# MainBoard_PWR.net
KiCad netlist of a schematic drawn in Altium Designer
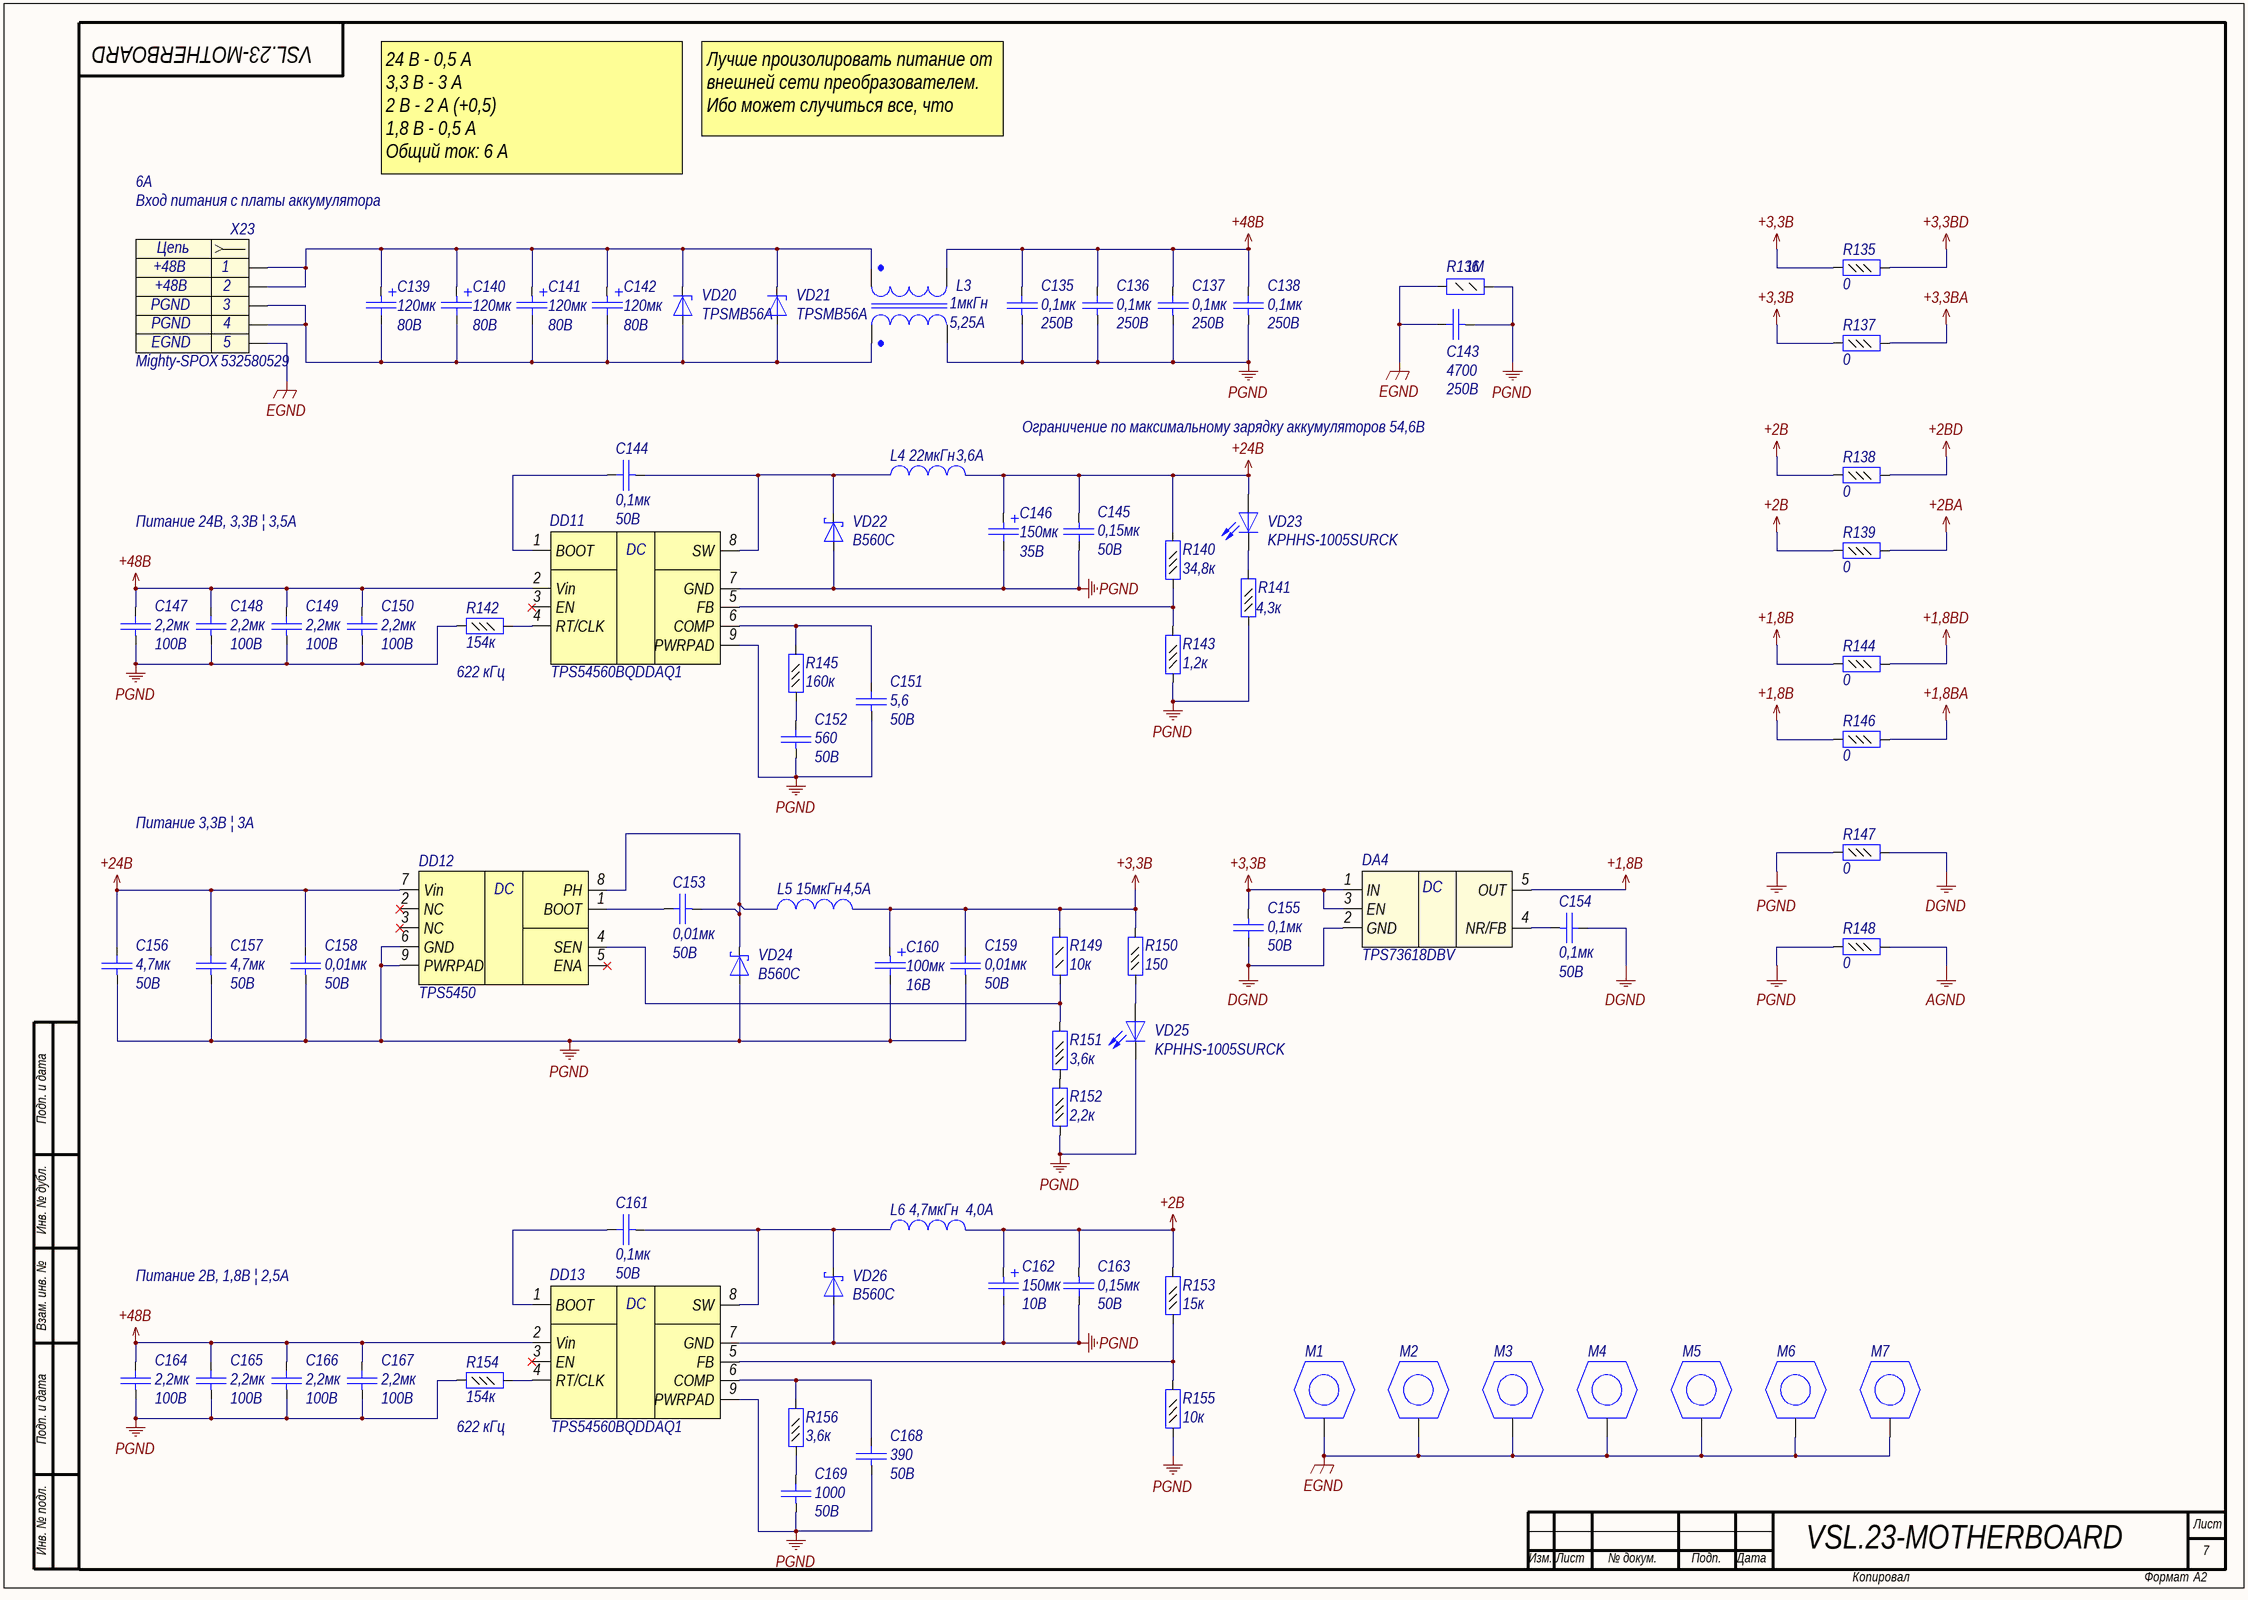
[diagram p0: MainBoard_PWR.SchDoc]

(export (version "E")
  (design (tool "Eeschema 10.0.6"))
  (components
    (comp (ref "C135")
      (value "0,1мк")
      (footprint "C1206")
      (description "Конденсатор")
      (fields
        (field (name "VOLTAGE") "250В")
        (field (name "PART NUMBER") "GRM31CR72E104K")
        (field (name "Comment") "Capacitor")
      )
      (libsource (lib "MOP44") (part "Capacitor"))
    )
    (comp (ref "C136")
      (value "0,1мк")
      (footprint "C1206")
      (description "Конденсатор")
      (fields
        (field (name "VOLTAGE") "250В")
        (field (name "PART NUMBER") "GRM31CR72E104K")
        (field (name "Comment") "Capacitor")
      )
      (libsource (lib "MOP44") (part "Capacitor"))
    )
    (comp (ref "C137")
      (value "0,1мк")
      (footprint "C1206")
      (description "Конденсатор")
      (fields
        (field (name "VOLTAGE") "250В")
        (field (name "PART NUMBER") "GRM31CR72E104K")
        (field (name "Comment") "Capacitor")
      )
      (libsource (lib "MOP44") (part "Capacitor"))
    )
    (comp (ref "C138")
      (value "0,1мк")
      (footprint "C1206")
      (description "Конденсатор")
      (fields
        (field (name "VOLTAGE") "250В")
        (field (name "PART NUMBER") "GRM31CR72E104K")
        (field (name "Comment") "Capacitor")
      )
      (libsource (lib "MOP44") (part "Capacitor"))
    )
    (comp (ref "C139")
      (value "120мк")
      (footprint "K50-35(8X20)_V")
      (description "Конденсатор полярный")
      (fields
        (field (name "VOLTAGE") "80В")
        (field (name "PART NUMBER") "EEU-FS1K121LB")
        (field (name "Comment") "Capacitor_pol")
      )
      (libsource (lib "MOP44") (part "Capacitor_pol"))
    )
    (comp (ref "C140")
      (value "120мк")
      (footprint "K50-35(8X20)_V")
      (description "Конденсатор полярный")
      (fields
        (field (name "VOLTAGE") "80В")
        (field (name "PART NUMBER") "EEU-FS1K121LB")
        (field (name "Comment") "Capacitor_pol")
      )
      (libsource (lib "MOP44") (part "Capacitor_pol"))
    )
    (comp (ref "C141")
      (value "120мк")
      (footprint "K50-35(8X20)_V")
      (description "Конденсатор полярный")
      (fields
        (field (name "VOLTAGE") "80В")
        (field (name "PART NUMBER") "EEU-FS1K121LB")
        (field (name "Comment") "Capacitor_pol")
      )
      (libsource (lib "MOP44") (part "Capacitor_pol"))
    )
    (comp (ref "C142")
      (value "120мк")
      (footprint "K50-35(8X20)_V")
      (description "Конденсатор полярный")
      (fields
        (field (name "VOLTAGE") "80В")
        (field (name "PART NUMBER") "EEU-FS1K121LB")
        (field (name "Comment") "Capacitor_pol")
      )
      (libsource (lib "MOP44") (part "Capacitor_pol"))
    )
    (comp (ref "C143")
      (value "4700")
      (footprint "C0805")
      (description "Конденсатор")
      (fields
        (field (name "VOLTAGE") "250В")
        (field (name "PART NUMBER") "GRM21AR72E472KW")
        (field (name "Comment") "Capacitor")
      )
      (libsource (lib "MOP44") (part "Capacitor"))
    )
    (comp (ref "C144")
      (value "0,1мк")
      (footprint "C0402")
      (description "Конденсатор")
      (fields (field (name "VOLTAGE") "50В") (field (name "PART NUMBER") "GRM155R71H104KE14D "))
      (libsource (lib "MOP44") (part "Capacitor"))
    )
    (comp (ref "C145")
      (value "0,15мк")
      (footprint "C1812")
      (description "Конденсатор")
      (fields (field (name "VOLTAGE") "50В") (field (name "PART NUMBER") "C4532C0G1H154J250KA "))
      (libsource (lib "MOP44") (part "Capacitor"))
    )
    (comp (ref "C146")
      (value "150мк")
      (footprint "Cap_SMD_radial_polar(8x10.2)")
      (description "Конденсатор полярный")
      (fields
        (field (name "VOLTAGE") "35В")
        (field (name "PART NUMBER") "EEH-ZE1V151V")
        (field (name "Comment") "Capacitor_pol")
      )
      (libsource (lib "MOP44") (part "Capacitor_pol"))
    )
    (comp (ref "C147")
      (value "2,2мк")
      (footprint "C1812")
      (description "Конденсатор")
      (fields (field (name "VOLTAGE") "100В") (field (name "PART NUMBER") "C4532X7R2A225M"))
      (libsource (lib "MOP44") (part "Capacitor"))
    )
    (comp (ref "C148")
      (value "2,2мк")
      (footprint "C1812")
      (description "Конденсатор")
      (fields (field (name "VOLTAGE") "100В") (field (name "PART NUMBER") "C4532X7R2A225M"))
      (libsource (lib "MOP44") (part "Capacitor"))
    )
    (comp (ref "C149")
      (value "2,2мк")
      (footprint "C1812")
      (description "Конденсатор")
      (fields (field (name "VOLTAGE") "100В") (field (name "PART NUMBER") "C4532X7R2A225M"))
      (libsource (lib "MOP44") (part "Capacitor"))
    )
    (comp (ref "C150")
      (value "2,2мк")
      (footprint "C1812")
      (description "Конденсатор")
      (fields (field (name "VOLTAGE") "100В") (field (name "PART NUMBER") "C4532X7R2A225M"))
      (libsource (lib "MOP44") (part "Capacitor"))
    )
    (comp (ref "C151")
      (value "5,6")
      (footprint "C0402")
      (description "Конденсатор")
      (fields (field (name "VOLTAGE") "50B") (field (name "PART NUMBER") "GRM1555C1H5R6C"))
      (libsource (lib "MOP44") (part "Capacitor"))
    )
    (comp (ref "C152")
      (value "560")
      (footprint "C0402")
      (description "Конденсатор")
      (fields (field (name "VOLTAGE") "50B") (field (name "PART NUMBER") "GRM1555C1H561J"))
      (libsource (lib "MOP44") (part "Capacitor"))
    )
    (comp (ref "C153")
      (value "0,01мк")
      (footprint "C0402")
      (description "Конденсатор")
      (fields (field (name "VOLTAGE") "50B") (field (name "PART NUMBER") "GRM155R71H103K"))
      (libsource (lib "MOP44") (part "Capacitor"))
    )
    (comp (ref "C154")
      (value "0,1мк")
      (footprint "C0402")
      (description "Конденсатор")
      (fields
        (field (name "VOLTAGE") "50В")
        (field (name "PART NUMBER") "GRM155R71H104KE14D ")
        (field (name "Comment") "Capacitor")
      )
      (libsource (lib "MOP44") (part "Capacitor"))
    )
    (comp (ref "C155")
      (value "0,1мк")
      (footprint "C0402")
      (description "Конденсатор")
      (fields
        (field (name "VOLTAGE") "50В")
        (field (name "PART NUMBER") "GRM155R71H104KE14D ")
        (field (name "Comment") "Capacitor")
      )
      (libsource (lib "MOP44") (part "Capacitor"))
    )
    (comp (ref "C156")
      (value "4,7мк")
      (footprint "C0805")
      (description "Конденсатор")
      (fields (field (name "VOLTAGE") "50В") (field (name "PART NUMBER") "GRM21BZ71H475KE15L"))
      (libsource (lib "MOP44") (part "Capacitor"))
    )
    (comp (ref "C157")
      (value "4,7мк")
      (footprint "C0805")
      (description "Конденсатор")
      (fields (field (name "VOLTAGE") "50В") (field (name "PART NUMBER") "GRM21BZ71H475KE15L"))
      (libsource (lib "MOP44") (part "Capacitor"))
    )
    (comp (ref "C158")
      (value "0,01мк")
      (footprint "C0402")
      (description "Конденсатор")
      (fields (field (name "VOLTAGE") "50B") (field (name "PART NUMBER") "GRM155R71H103K"))
      (libsource (lib "MOP44") (part "Capacitor"))
    )
    (comp (ref "C159")
      (value "0,01мк")
      (footprint "C0402")
      (description "Конденсатор")
      (fields (field (name "VOLTAGE") "50B") (field (name "PART NUMBER") "GRM155R71H103K"))
      (libsource (lib "MOP44") (part "Capacitor"))
    )
    (comp (ref "C160")
      (value "100мк")
      (footprint "TANTAL CASE D")
      (description "Конденсатор полярный")
      (fields
        (field (name "VOLTAGE") "16В")
        (field (name "PART NUMBER") "293D107X9016D2TE3")
        (field (name "Comment") "Capacitor_pol")
      )
      (libsource (lib "MOP44") (part "Capacitor_pol"))
    )
    (comp (ref "C161")
      (value "0,1мк")
      (footprint "C0402")
      (description "Конденсатор")
      (fields (field (name "VOLTAGE") "50В") (field (name "PART NUMBER") "GRM155R71H104KE14D "))
      (libsource (lib "MOP44") (part "Capacitor"))
    )
    (comp (ref "C162")
      (value "150мк")
      (footprint "TANTAL CASE D")
      (description "Конденсатор полярный")
      (fields
        (field (name "VOLTAGE") "10B")
        (field (name "PART NUMBER") "TPSD157K010R0050")
        (field (name "Comment") "Capacitor_pol")
      )
      (libsource (lib "MOP44") (part "Capacitor_pol"))
    )
    (comp (ref "C163")
      (value "0,15мк")
      (footprint "C1812")
      (description "Конденсатор")
      (fields (field (name "VOLTAGE") "50В") (field (name "PART NUMBER") "C4532C0G1H154J250KA "))
      (libsource (lib "MOP44") (part "Capacitor"))
    )
    (comp (ref "C164")
      (value "2,2мк")
      (footprint "C1812")
      (description "Конденсатор")
      (fields (field (name "VOLTAGE") "100В") (field (name "PART NUMBER") "C4532X7R2A225M"))
      (libsource (lib "MOP44") (part "Capacitor"))
    )
    (comp (ref "C165")
      (value "2,2мк")
      (footprint "C1812")
      (description "Конденсатор")
      (fields (field (name "VOLTAGE") "100В") (field (name "PART NUMBER") "C4532X7R2A225M"))
      (libsource (lib "MOP44") (part "Capacitor"))
    )
    (comp (ref "C166")
      (value "2,2мк")
      (footprint "C1812")
      (description "Конденсатор")
      (fields (field (name "VOLTAGE") "100В") (field (name "PART NUMBER") "C4532X7R2A225M"))
      (libsource (lib "MOP44") (part "Capacitor"))
    )
    (comp (ref "C167")
      (value "2,2мк")
      (footprint "C1812")
      (description "Конденсатор")
      (fields (field (name "VOLTAGE") "100В") (field (name "PART NUMBER") "C4532X7R2A225M"))
      (libsource (lib "MOP44") (part "Capacitor"))
    )
    (comp (ref "C168")
      (value "390")
      (footprint "C0402")
      (description "Конденсатор")
      (fields (field (name "VOLTAGE") "50B") (field (name "PART NUMBER") "GRM1555C1H391J"))
      (libsource (lib "MOP44") (part "Capacitor"))
    )
    (comp (ref "C169")
      (value "1000")
      (footprint "C0402")
      (description "Конденсатор")
      (fields (field (name "VOLTAGE") "50B") (field (name "PART NUMBER") "GRM1555C1H102J"))
      (libsource (lib "MOP44") (part "Capacitor"))
    )
    (comp (ref "DA4")
      (value "TPS736DBV")
      (footprint "SOT23-5")
      (description "400-mA Low-Dropout Regulator with Reverse Current  Protection")
      (fields (field (name "PART NUMBER") "TPS73618DBV") (field (name "MANUFACTURER") "Texas Instruments"))
      (libsource (lib "MOP44") (part "TPS736DBV"))
    )
    (comp (ref "DD11")
      (value "TPS54560")
      (footprint "SO Powerpad8")
      (description "5-A, Wide Input Range, Step-Down Converter")
      (fields
        (field (name "PART NUMBER") "TPS54560BQDDAQ1")
        (field (name "MANUFACTURER") "Texas Instruments")
      )
      (libsource (lib "MOP44") (part "TPS54560"))
    )
    (comp (ref "DD12")
      (value "TPS5450")
      (footprint "SO Powerpad8")
      (description "5-A, Wide Input Range, Step-Down Converter")
      (fields (field (name "PART NUMBER") "TPS5450") (field (name "MANUFACTURER") "Texas Instruments"))
      (libsource (lib "MOP44") (part "TPS5450"))
    )
    (comp (ref "DD13")
      (value "TPS54560")
      (footprint "SO Powerpad8")
      (description "5-A, Wide Input Range, Step-Down Converter")
      (fields
        (field (name "PART NUMBER") "TPS54560BQDDAQ1")
        (field (name "MANUFACTURER") "Texas Instruments")
      )
      (libsource (lib "MOP44") (part "TPS54560"))
    )
    (comp (ref "L3")
      (value "1мкГн")
      (footprint "SRF0703")
      (description "Синфазный дроссель")
      (fields
        (field (name "RATED CURRENT") "5,25A")
        (field (name "PART NUMBER") "SRF0703-1R0M")
        (field (name "Comment") "Dual-Winding Inductor")
      )
      (libsource (lib "MOP44") (part "Dual-Winding Inductor"))
    )
    (comp (ref "L4")
      (value "22мкГн")
      (footprint "IND_12.5x12.5")
      (description "EMI Suppression Filter")
      (fields
        (field (name "RATED CURRENT") "3,6A")
        (field (name "PART NUMBER") "B82477G4223M000")
        (field (name "Comment") "Inductor")
      )
      (libsource (lib "MOP44") (part "Inductor"))
    )
    (comp (ref "L5")
      (value "15мкГн")
      (footprint "IND_12.5x12.5")
      (description "EMI Suppression Filter")
      (fields
        (field (name "RATED CURRENT") "4,5A")
        (field (name "PART NUMBER") "B82477G4153M000")
        (field (name "Comment") "Inductor")
      )
      (libsource (lib "MOP44") (part "Inductor"))
    )
    (comp (ref "L6")
      (value "4,7мкГн")
      (footprint "SDR1006")
      (description "EMI Suppression Filter")
      (fields
        (field (name "RATED CURRENT") "4,0A")
        (field (name "PART NUMBER") "SDR1006-4R7ML")
        (field (name "Comment") "Inductor")
      )
      (libsource (lib "MOP44") (part "Inductor"))
    )
    (comp (ref "M1") (value "SCREW") (footprint "SCREW3") (libsource (lib "MOP44") (part "SCREW")))
    (comp (ref "M2") (value "SCREW") (footprint "SCREW3") (libsource (lib "MOP44") (part "SCREW")))
    (comp (ref "M3") (value "SCREW") (footprint "SCREW3") (libsource (lib "MOP44") (part "SCREW")))
    (comp (ref "M4") (value "SCREW") (footprint "SCREW3") (libsource (lib "MOP44") (part "SCREW")))
    (comp (ref "M5") (value "SCREW") (footprint "SCREW3") (libsource (lib "MOP44") (part "SCREW")))
    (comp (ref "M6") (value "SCREW") (footprint "SCREW3") (libsource (lib "MOP44") (part "SCREW")))
    (comp (ref "M7") (value "SCREW") (footprint "SCREW3") (libsource (lib "MOP44") (part "SCREW")))
    (comp (ref "R135")
      (value "0")
      (footprint "R0402")
      (description "Резистор")
      (fields (field (name "PART NUMBER") "RC0603FR-070RL") (field (name "POWER") "0,062Вт"))
      (libsource (lib "") (part "Resistor_0,062Вт_1"))
    )
    (comp (ref "R136")
      (value "1М")
      (footprint "R0805")
      (description "Резистор")
      (fields (field (name "PART NUMBER") "RC0805FR-071ML") (field (name "POWER") "0,125Вт"))
      (libsource (lib "MOP44") (part "Resistor_0,125Вт"))
    )
    (comp (ref "R137")
      (value "0")
      (footprint "R0402")
      (description "Резистор")
      (fields (field (name "PART NUMBER") "RC0603FR-070RL") (field (name "POWER") "0,062Вт"))
      (libsource (lib "") (part "Resistor_0,062Вт_1"))
    )
    (comp (ref "R138")
      (value "0")
      (footprint "R0402")
      (description "Резистор")
      (fields (field (name "PART NUMBER") "RC0603FR-070RL") (field (name "POWER") "0,062Вт"))
      (libsource (lib "") (part "Resistor_0,062Вт_1"))
    )
    (comp (ref "R139")
      (value "0")
      (footprint "R0402")
      (description "Резистор")
      (fields (field (name "PART NUMBER") "RC0603FR-070RL") (field (name "POWER") "0,062Вт"))
      (libsource (lib "") (part "Resistor_0,062Вт_1"))
    )
    (comp (ref "R140")
      (value "34,8к")
      (footprint "R0402")
      (description "Резистор")
      (fields (field (name "PART NUMBER") "RC0402FR-0734K8L") (field (name "POWER") "0,062Вт"))
      (libsource (lib "MOP44") (part "Resistor_0,062Вт"))
    )
    (comp (ref "R141")
      (value "4,3к")
      (footprint "R0402")
      (description "Резистор")
      (fields (field (name "PART NUMBER") "RC0402FR-074K3") (field (name "POWER") "0,062Вт"))
      (libsource (lib "MOP44") (part "Resistor_0,062Вт"))
    )
    (comp (ref "R142")
      (value "154к")
      (footprint "R0402")
      (description "Резистор")
      (fields (field (name "PART NUMBER") "RC0402FR-07154KL") (field (name "POWER") "0,062Вт"))
      (libsource (lib "") (part "Resistor_0,062Вт_1"))
    )
    (comp (ref "R143")
      (value "1,2к")
      (footprint "R0402")
      (description "Резистор")
      (fields (field (name "PART NUMBER") "RC0402FR-071K2") (field (name "POWER") "0,062Вт"))
      (libsource (lib "MOP44") (part "Resistor_0,062Вт"))
    )
    (comp (ref "R144")
      (value "0")
      (footprint "R0402")
      (description "Резистор")
      (fields (field (name "PART NUMBER") "RC0603FR-070RL") (field (name "POWER") "0,062Вт"))
      (libsource (lib "") (part "Resistor_0,062Вт_1"))
    )
    (comp (ref "R145")
      (value "160к")
      (footprint "R0402")
      (description "Резистор")
      (fields (field (name "PART NUMBER") "RC0402FR-07160KL") (field (name "POWER") "0,062Вт"))
      (libsource (lib "MOP44") (part "Resistor_0,062Вт"))
    )
    (comp (ref "R146")
      (value "0")
      (footprint "R0402")
      (description "Резистор")
      (fields (field (name "PART NUMBER") "RC0603FR-070RL") (field (name "POWER") "0,062Вт"))
      (libsource (lib "") (part "Resistor_0,062Вт_1"))
    )
    (comp (ref "R147")
      (value "0")
      (footprint "R0402")
      (description "Резистор")
      (fields (field (name "PART NUMBER") "RC0603FR-070RL") (field (name "POWER") "0,062Вт"))
      (libsource (lib "") (part "Resistor_0,062Вт_1"))
    )
    (comp (ref "R148")
      (value "0")
      (footprint "R0402")
      (description "Резистор")
      (fields (field (name "PART NUMBER") "RC0603FR-070RL") (field (name "POWER") "0,062Вт"))
      (libsource (lib "") (part "Resistor_0,062Вт_1"))
    )
    (comp (ref "R149")
      (value "10к")
      (footprint "R0402")
      (description "Резистор")
      (fields (field (name "PART NUMBER") "RC0805FR-0710KL") (field (name "POWER") "0,125Вт"))
      (libsource (lib "") (part "Resistor_0,125Вт_1"))
    )
    (comp (ref "R150")
      (value "150")
      (footprint "R0402")
      (description "Резистор")
      (fields (field (name "PART NUMBER") "RC0402FR-07150RL") (field (name "POWER") "0,062Вт"))
      (libsource (lib "MOP44") (part "Resistor_0,062Вт"))
    )
    (comp (ref "R151")
      (value "3,6к")
      (footprint "R0402")
      (description "Резистор")
      (fields (field (name "PART NUMBER") "RC0402FR-072K6") (field (name "POWER") "0,062Вт"))
      (libsource (lib "MOP44") (part "Resistor_0,062Вт"))
    )
    (comp (ref "R152")
      (value "2,2к")
      (footprint "R0402")
      (description "Резистор")
      (fields (field (name "PART NUMBER") "RC0402FR-072K2") (field (name "POWER") "0,062Вт"))
      (libsource (lib "MOP44") (part "Resistor_0,062Вт"))
    )
    (comp (ref "R153")
      (value "15к")
      (footprint "R0402")
      (description "Резистор")
      (fields (field (name "PART NUMBER") "RC0603FR-0715KL") (field (name "POWER") "0,062Вт"))
      (libsource (lib "MOP44") (part "Resistor_0,062Вт"))
    )
    (comp (ref "R154")
      (value "154к")
      (footprint "R0402")
      (description "Резистор")
      (fields (field (name "PART NUMBER") "RC0402FR-07154KL") (field (name "POWER") "0,062Вт"))
      (libsource (lib "") (part "Resistor_0,062Вт_1"))
    )
    (comp (ref "R155")
      (value "10к")
      (footprint "R0402")
      (description "Резистор")
      (fields (field (name "PART NUMBER") "RC0603FR-0710KL") (field (name "POWER") "0,062Вт"))
      (libsource (lib "MOP44") (part "Resistor_0,062Вт"))
    )
    (comp (ref "R156")
      (value "3,6к")
      (footprint "R0402")
      (description "Резистор")
      (fields (field (name "PART NUMBER") "RC0402FR-072K6") (field (name "POWER") "0,062Вт"))
      (libsource (lib "MOP44") (part "Resistor_0,062Вт"))
    )
    (comp (ref "VD20")
      (value "DiodeZener")
      (footprint "SMB")
      (description "Cтабилитрон (лавинный выпрямительный диод) односторонний")
      (fields (field (name "PART NUMBER") "TPSMB56A"))
      (libsource (lib "MOP44") (part "DiodeZener"))
    )
    (comp (ref "VD21")
      (value "DiodeZener")
      (footprint "SMB")
      (description "Cтабилитрон (лавинный выпрямительный диод) односторонний")
      (fields (field (name "PART NUMBER") "TPSMB56A"))
      (libsource (lib "MOP44") (part "DiodeZener"))
    )
    (comp (ref "VD22")
      (value "DiodeSchottky")
      (footprint "SMC")
      (description "Диод Шоттки")
      (fields (field (name "PART NUMBER") "B560C"))
      (libsource (lib "MOP44") (part "DiodeSchottky"))
    )
    (comp (ref "VD23")
      (value "LED")
      (footprint "L_0402_RED")
      (description "Светодиод")
      (fields (field (name "PART NUMBER") "KPHHS-1005SURCK"))
      (libsource (lib "MOP44") (part "LED"))
    )
    (comp (ref "VD24")
      (value "DiodeSchottky")
      (footprint "SMC")
      (description "Диод Шоттки")
      (fields (field (name "PART NUMBER") "B560C"))
      (libsource (lib "MOP44") (part "DiodeSchottky"))
    )
    (comp (ref "VD25")
      (value "LED")
      (footprint "L_0402_RED")
      (description "Светодиод")
      (fields (field (name "PART NUMBER") "KPHHS-1005SURCK"))
      (libsource (lib "MOP44") (part "LED"))
    )
    (comp (ref "VD26")
      (value "DiodeSchottky")
      (footprint "SMC")
      (description "Диод Шоттки")
      (fields (field (name "PART NUMBER") "B560C"))
      (libsource (lib "MOP44") (part "DiodeSchottky"))
    )
    (comp (ref "X23")
      (value "Header_5_sct")
      (footprint "MOLEX_532580529")
      (description "Разъем - 5 конт. розетка")
      (fields (field (name "PART NAME") "Mighty-SPOX") (field (name "PART NUMBER") "532580529"))
      (libsource (lib "MOP44") (part "Header_5_sct"))
    )
  )
  (nets
    (net (code "1") (name "+1,8B") (class "Default")
      (node (ref "DA4") (pin "5") (pinfunction "OUT_5") (pintype "power_in"))
      (node (ref "R144") (pin "1") (pinfunction "1_1") (pintype "passive"))
      (node (ref "R146") (pin "1") (pinfunction "1_1") (pintype "passive"))
    )
    (net (code "2") (name "+1,8BA") (class "Default")
      (node (ref "R146") (pin "2") (pinfunction "2_2") (pintype "passive"))
    )
    (net (code "3") (name "+1,8BD") (class "Default")
      (node (ref "R144") (pin "2") (pinfunction "2_2") (pintype "passive"))
    )
    (net (code "4") (name "+2B") (class "Default")
      (node (ref "C162") (pin "1") (pinfunction "1_1") (pintype "passive"))
      (node (ref "C163") (pin "1") (pinfunction "1_1") (pintype "passive"))
      (node (ref "L6") (pin "2") (pinfunction "2_2") (pintype "passive"))
      (node (ref "R138") (pin "1") (pinfunction "1_1") (pintype "passive"))
      (node (ref "R139") (pin "1") (pinfunction "1_1") (pintype "passive"))
      (node (ref "R153") (pin "2") (pinfunction "2_2") (pintype "passive"))
    )
    (net (code "5") (name "+2BA") (class "Default")
      (node (ref "R139") (pin "2") (pinfunction "2_2") (pintype "passive"))
    )
    (net (code "6") (name "+2BD") (class "Default")
      (node (ref "R138") (pin "2") (pinfunction "2_2") (pintype "passive"))
    )
    (net (code "7") (name "+3,3B") (class "Default")
      (node (ref "C155") (pin "1") (pinfunction "1_1") (pintype "passive"))
      (node (ref "C159") (pin "2") (pinfunction "2_2") (pintype "passive"))
      (node (ref "C160") (pin "1") (pinfunction "1_1") (pintype "passive"))
      (node (ref "DA4") (pin "1") (pinfunction "IN_1") (pintype "power_in"))
      (node (ref "DA4") (pin "3") (pinfunction "EN_3") (pintype "power_in"))
      (node (ref "L5") (pin "2") (pinfunction "2_2") (pintype "passive"))
      (node (ref "R135") (pin "1") (pinfunction "1_1") (pintype "passive"))
      (node (ref "R137") (pin "1") (pinfunction "1_1") (pintype "passive"))
      (node (ref "R149") (pin "2") (pinfunction "2_2") (pintype "passive"))
      (node (ref "R150") (pin "2") (pinfunction "2_2") (pintype "passive"))
    )
    (net (code "8") (name "+3,3BA") (class "Default")
      (node (ref "R137") (pin "2") (pinfunction "2_2") (pintype "passive"))
    )
    (net (code "9") (name "+3,3BD") (class "Default")
      (node (ref "R135") (pin "2") (pinfunction "2_2") (pintype "passive"))
    )
    (net (code "10") (name "+24B") (class "Default")
      (node (ref "C145") (pin "1") (pinfunction "1_1") (pintype "passive"))
      (node (ref "C146") (pin "1") (pinfunction "1_1") (pintype "passive"))
      (node (ref "C156") (pin "2") (pinfunction "2_2") (pintype "passive"))
      (node (ref "C157") (pin "2") (pinfunction "2_2") (pintype "passive"))
      (node (ref "C158") (pin "2") (pinfunction "2_2") (pintype "passive"))
      (node (ref "DD12") (pin "7") (pinfunction "Vin_7") (pintype "passive"))
      (node (ref "L4") (pin "2") (pinfunction "2_2") (pintype "passive"))
      (node (ref "R140") (pin "2") (pinfunction "2_2") (pintype "passive"))
      (node (ref "VD23") (pin "2") (pinfunction "A_2") (pintype "passive"))
    )
    (net (code "11") (name "+48B") (class "Default")
      (node (ref "C135") (pin "2") (pinfunction "2_2") (pintype "passive"))
      (node (ref "C136") (pin "2") (pinfunction "2_2") (pintype "passive"))
      (node (ref "C137") (pin "2") (pinfunction "2_2") (pintype "passive"))
      (node (ref "C138") (pin "2") (pinfunction "2_2") (pintype "passive"))
      (node (ref "C147") (pin "2") (pinfunction "2_2") (pintype "passive"))
      (node (ref "C148") (pin "2") (pinfunction "2_2") (pintype "passive"))
      (node (ref "C149") (pin "2") (pinfunction "2_2") (pintype "passive"))
      (node (ref "C150") (pin "2") (pinfunction "2_2") (pintype "passive"))
      (node (ref "C164") (pin "2") (pinfunction "2_2") (pintype "passive"))
      (node (ref "C165") (pin "2") (pinfunction "2_2") (pintype "passive"))
      (node (ref "C166") (pin "2") (pinfunction "2_2") (pintype "passive"))
      (node (ref "C167") (pin "2") (pinfunction "2_2") (pintype "passive"))
      (node (ref "DD11") (pin "2") (pinfunction "Vin_2") (pintype "passive"))
      (node (ref "DD13") (pin "2") (pinfunction "Vin_2") (pintype "passive"))
      (node (ref "L3") (pin "4") (pintype "passive"))
    )
    (net (code "12") (name "AGND") (class "Default")
      (node (ref "R148") (pin "2") (pinfunction "2_2") (pintype "passive"))
    )
    (net (code "13") (name "DGND") (class "Default")
      (node (ref "C154") (pin "2") (pinfunction "2_2") (pintype "passive"))
      (node (ref "C155") (pin "2") (pinfunction "2_2") (pintype "passive"))
      (node (ref "DA4") (pin "2") (pinfunction "GND_2") (pintype "power_in"))
      (node (ref "R147") (pin "2") (pinfunction "2_2") (pintype "passive"))
    )
    (net (code "14") (name "EGND") (class "Default")
      (node (ref "C143") (pin "2") (pinfunction "2_2") (pintype "passive"))
      (node (ref "M1") (pin "1") (pinfunction "1_1") (pintype "passive"))
      (node (ref "M2") (pin "1") (pinfunction "1_1") (pintype "passive"))
      (node (ref "M3") (pin "1") (pinfunction "1_1") (pintype "passive"))
      (node (ref "M4") (pin "1") (pinfunction "1_1") (pintype "passive"))
      (node (ref "M5") (pin "1") (pinfunction "1_1") (pintype "passive"))
      (node (ref "M6") (pin "1") (pinfunction "1_1") (pintype "passive"))
      (node (ref "M7") (pin "1") (pinfunction "1_1") (pintype "passive"))
      (node (ref "R136") (pin "2") (pinfunction "2_2") (pintype "passive"))
      (node (ref "X23") (pin "5") (pinfunction "5_5") (pintype "passive"))
    )
    (net (code "15") (name "Net-(C152-Pad2)") (class "Default")
      (node (ref "C152") (pin "2") (pinfunction "2_2") (pintype "passive"))
      (node (ref "R145") (pin "1") (pinfunction "1_1") (pintype "passive"))
    )
    (net (code "16") (name "Net-(C169-Pad2)") (class "Default")
      (node (ref "C169") (pin "2") (pinfunction "2_2") (pintype "passive"))
      (node (ref "R156") (pin "1") (pinfunction "1_1") (pintype "passive"))
    )
    (net (code "17") (name "Net-(DA4-NR{slash}FB)") (class "Default")
      (node (ref "C154") (pin "1") (pinfunction "1_1") (pintype "passive"))
      (node (ref "DA4") (pin "4") (pinfunction "NR/FB_4") (pintype "power_in"))
    )
    (net (code "18") (name "Net-(DD11-BOOT)") (class "Default")
      (node (ref "C144") (pin "2") (pinfunction "2_2") (pintype "passive"))
      (node (ref "DD11") (pin "1") (pinfunction "BOOT_1") (pintype "passive"))
    )
    (net (code "19") (name "Net-(DD11-COMP)") (class "Default")
      (node (ref "C151") (pin "2") (pinfunction "2_2") (pintype "passive"))
      (node (ref "DD11") (pin "6") (pinfunction "COMP_6") (pintype "passive"))
      (node (ref "R145") (pin "2") (pinfunction "2_2") (pintype "passive"))
    )
    (net (code "20") (name "Net-(DD11-FB)") (class "Default")
      (node (ref "DD11") (pin "5") (pinfunction "FB_5") (pintype "passive"))
      (node (ref "R140") (pin "1") (pinfunction "1_1") (pintype "passive"))
      (node (ref "R143") (pin "2") (pinfunction "2_2") (pintype "passive"))
    )
    (net (code "21") (name "Net-(DD11-RT{slash}CLK)") (class "Default")
      (node (ref "DD11") (pin "4") (pinfunction "RT/CLK_4") (pintype "passive"))
      (node (ref "R142") (pin "2") (pinfunction "2_2") (pintype "passive"))
    )
    (net (code "22") (name "Net-(DD11-SW)") (class "Default")
      (node (ref "C144") (pin "1") (pinfunction "1_1") (pintype "passive"))
      (node (ref "DD11") (pin "8") (pinfunction "SW_8") (pintype "passive"))
      (node (ref "L4") (pin "1") (pinfunction "1_1") (pintype "passive"))
      (node (ref "VD22") (pin "1") (pinfunction "K_1") (pintype "passive"))
    )
    (net (code "23") (name "Net-(DD12-BOOT)") (class "Default")
      (node (ref "C153") (pin "2") (pinfunction "2_2") (pintype "passive"))
      (node (ref "DD12") (pin "1") (pinfunction "BOOT_1") (pintype "passive"))
    )
    (net (code "24") (name "Net-(DD12-PH)") (class "Default")
      (node (ref "C153") (pin "1") (pinfunction "1_1") (pintype "passive"))
      (node (ref "DD12") (pin "8") (pinfunction "PH_8") (pintype "passive"))
      (node (ref "L5") (pin "1") (pinfunction "1_1") (pintype "passive"))
      (node (ref "VD24") (pin "1") (pinfunction "K_1") (pintype "passive"))
    )
    (net (code "25") (name "Net-(DD12-SEN)") (class "Default")
      (node (ref "DD12") (pin "4") (pinfunction "SEN_4") (pintype "passive"))
      (node (ref "R149") (pin "1") (pinfunction "1_1") (pintype "passive"))
      (node (ref "R151") (pin "2") (pinfunction "2_2") (pintype "passive"))
    )
    (net (code "26") (name "Net-(DD13-BOOT)") (class "Default")
      (node (ref "C161") (pin "2") (pinfunction "2_2") (pintype "passive"))
      (node (ref "DD13") (pin "1") (pinfunction "BOOT_1") (pintype "passive"))
    )
    (net (code "27") (name "Net-(DD13-COMP)") (class "Default")
      (node (ref "C168") (pin "2") (pinfunction "2_2") (pintype "passive"))
      (node (ref "DD13") (pin "6") (pinfunction "COMP_6") (pintype "passive"))
      (node (ref "R156") (pin "2") (pinfunction "2_2") (pintype "passive"))
    )
    (net (code "28") (name "Net-(DD13-FB)") (class "Default")
      (node (ref "DD13") (pin "5") (pinfunction "FB_5") (pintype "passive"))
      (node (ref "R153") (pin "1") (pinfunction "1_1") (pintype "passive"))
      (node (ref "R155") (pin "2") (pinfunction "2_2") (pintype "passive"))
    )
    (net (code "29") (name "Net-(DD13-RT{slash}CLK)") (class "Default")
      (node (ref "DD13") (pin "4") (pinfunction "RT/CLK_4") (pintype "passive"))
      (node (ref "R154") (pin "2") (pinfunction "2_2") (pintype "passive"))
    )
    (net (code "30") (name "Net-(DD13-SW)") (class "Default")
      (node (ref "C161") (pin "1") (pinfunction "1_1") (pintype "passive"))
      (node (ref "DD13") (pin "8") (pinfunction "SW_8") (pintype "passive"))
      (node (ref "L6") (pin "1") (pinfunction "1_1") (pintype "passive"))
      (node (ref "VD26") (pin "1") (pinfunction "K_1") (pintype "passive"))
    )
    (net (code "31") (name "Net-(R151-Pad1)") (class "Default")
      (node (ref "R151") (pin "1") (pinfunction "1_1") (pintype "passive"))
      (node (ref "R152") (pin "2") (pinfunction "2_2") (pintype "passive"))
    )
    (net (code "32") (name "Net-(VD20-A)") (class "Default")
      (node (ref "C139") (pin "2") (pinfunction "2_2") (pintype "passive"))
      (node (ref "C140") (pin "2") (pinfunction "2_2") (pintype "passive"))
      (node (ref "C141") (pin "2") (pinfunction "2_2") (pintype "passive"))
      (node (ref "C142") (pin "2") (pinfunction "2_2") (pintype "passive"))
      (node (ref "L3") (pin "1") (pintype "passive"))
      (node (ref "VD20") (pin "2") (pinfunction "A_2") (pintype "passive"))
      (node (ref "VD21") (pin "2") (pinfunction "A_2") (pintype "passive"))
      (node (ref "X23") (pin "3") (pinfunction "3_3") (pintype "passive"))
      (node (ref "X23") (pin "4") (pinfunction "4_4") (pintype "passive"))
    )
    (net (code "33") (name "Net-(VD20-K)") (class "Default")
      (node (ref "C139") (pin "1") (pinfunction "1_1") (pintype "passive"))
      (node (ref "C140") (pin "1") (pinfunction "1_1") (pintype "passive"))
      (node (ref "C141") (pin "1") (pinfunction "1_1") (pintype "passive"))
      (node (ref "C142") (pin "1") (pinfunction "1_1") (pintype "passive"))
      (node (ref "L3") (pin "2") (pintype "passive"))
      (node (ref "VD20") (pin "1") (pinfunction "K_1") (pintype "passive"))
      (node (ref "VD21") (pin "1") (pinfunction "K_1") (pintype "passive"))
      (node (ref "X23") (pin "1") (pinfunction "1_1") (pintype "passive"))
      (node (ref "X23") (pin "2") (pinfunction "2_2") (pintype "passive"))
    )
    (net (code "34") (name "Net-(VD23-K)") (class "Default")
      (node (ref "R141") (pin "2") (pinfunction "2_2") (pintype "passive"))
      (node (ref "VD23") (pin "1") (pinfunction "K_1") (pintype "passive"))
    )
    (net (code "35") (name "Net-(VD25-A)") (class "Default")
      (node (ref "R150") (pin "1") (pinfunction "1_1") (pintype "passive"))
      (node (ref "VD25") (pin "2") (pinfunction "A_2") (pintype "passive"))
    )
    (net (code "36") (name "PGND") (class "Default")
      (node (ref "C135") (pin "1") (pinfunction "1_1") (pintype "passive"))
      (node (ref "C136") (pin "1") (pinfunction "1_1") (pintype "passive"))
      (node (ref "C137") (pin "1") (pinfunction "1_1") (pintype "passive"))
      (node (ref "C138") (pin "1") (pinfunction "1_1") (pintype "passive"))
      (node (ref "C143") (pin "1") (pinfunction "1_1") (pintype "passive"))
      (node (ref "C145") (pin "2") (pinfunction "2_2") (pintype "passive"))
      (node (ref "C146") (pin "2") (pinfunction "2_2") (pintype "passive"))
      (node (ref "C147") (pin "1") (pinfunction "1_1") (pintype "passive"))
      (node (ref "C148") (pin "1") (pinfunction "1_1") (pintype "passive"))
      (node (ref "C149") (pin "1") (pinfunction "1_1") (pintype "passive"))
      (node (ref "C150") (pin "1") (pinfunction "1_1") (pintype "passive"))
      (node (ref "C151") (pin "1") (pinfunction "1_1") (pintype "passive"))
      (node (ref "C152") (pin "1") (pinfunction "1_1") (pintype "passive"))
      (node (ref "C156") (pin "1") (pinfunction "1_1") (pintype "passive"))
      (node (ref "C157") (pin "1") (pinfunction "1_1") (pintype "passive"))
      (node (ref "C158") (pin "1") (pinfunction "1_1") (pintype "passive"))
      (node (ref "C159") (pin "1") (pinfunction "1_1") (pintype "passive"))
      (node (ref "C160") (pin "2") (pinfunction "2_2") (pintype "passive"))
      (node (ref "C162") (pin "2") (pinfunction "2_2") (pintype "passive"))
      (node (ref "C163") (pin "2") (pinfunction "2_2") (pintype "passive"))
      (node (ref "C164") (pin "1") (pinfunction "1_1") (pintype "passive"))
      (node (ref "C165") (pin "1") (pinfunction "1_1") (pintype "passive"))
      (node (ref "C166") (pin "1") (pinfunction "1_1") (pintype "passive"))
      (node (ref "C167") (pin "1") (pinfunction "1_1") (pintype "passive"))
      (node (ref "C168") (pin "1") (pinfunction "1_1") (pintype "passive"))
      (node (ref "C169") (pin "1") (pinfunction "1_1") (pintype "passive"))
      (node (ref "DD11") (pin "7") (pinfunction "GND_7") (pintype "passive"))
      (node (ref "DD11") (pin "9") (pinfunction "PWRPAD_9") (pintype "passive"))
      (node (ref "DD12") (pin "6") (pinfunction "GND_6") (pintype "passive"))
      (node (ref "DD12") (pin "9") (pinfunction "PWRPAD_9") (pintype "passive"))
      (node (ref "DD13") (pin "7") (pinfunction "GND_7") (pintype "passive"))
      (node (ref "DD13") (pin "9") (pinfunction "PWRPAD_9") (pintype "passive"))
      (node (ref "L3") (pin "3") (pintype "passive"))
      (node (ref "R136") (pin "1") (pinfunction "1_1") (pintype "passive"))
      (node (ref "R141") (pin "1") (pinfunction "1_1") (pintype "passive"))
      (node (ref "R142") (pin "1") (pinfunction "1_1") (pintype "passive"))
      (node (ref "R143") (pin "1") (pinfunction "1_1") (pintype "passive"))
      (node (ref "R147") (pin "1") (pinfunction "1_1") (pintype "passive"))
      (node (ref "R148") (pin "1") (pinfunction "1_1") (pintype "passive"))
      (node (ref "R152") (pin "1") (pinfunction "1_1") (pintype "passive"))
      (node (ref "R154") (pin "1") (pinfunction "1_1") (pintype "passive"))
      (node (ref "R155") (pin "1") (pinfunction "1_1") (pintype "passive"))
      (node (ref "VD22") (pin "2") (pinfunction "A_2") (pintype "passive"))
      (node (ref "VD24") (pin "2") (pinfunction "A_2") (pintype "passive"))
      (node (ref "VD25") (pin "1") (pinfunction "K_1") (pintype "passive"))
      (node (ref "VD26") (pin "2") (pinfunction "A_2") (pintype "passive"))
    )
    (net (code "37") (name "unconnected-(DD11-EN-Pad3)") (class "Default")
      (node (ref "DD11") (pin "3") (pinfunction "EN_3") (pintype "passive+no_connect"))
    )
    (net (code "38") (name "unconnected-(DD12-ENA-Pad5)") (class "Default")
      (node (ref "DD12") (pin "5") (pinfunction "ENA_5") (pintype "passive+no_connect"))
    )
    (net (code "39") (name "unconnected-(DD12-NC-Pad2)") (class "Default")
      (node (ref "DD12") (pin "2") (pinfunction "NC_2") (pintype "passive+no_connect"))
    )
    (net (code "40") (name "unconnected-(DD12-NC-Pad3)") (class "Default")
      (node (ref "DD12") (pin "3") (pinfunction "NC_3") (pintype "passive+no_connect"))
    )
    (net (code "41") (name "unconnected-(DD13-EN-Pad3)") (class "Default")
      (node (ref "DD13") (pin "3") (pinfunction "EN_3") (pintype "passive+no_connect"))
    )
  )
)
